# Power-Resistor-Breakout-3W-v001.net
KiCad netlist of a schematic drawn in EAGLE
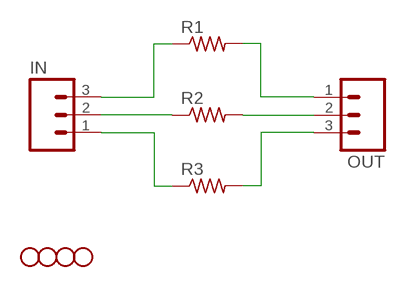
[diagram p0: schematic, sheet 1]

(export (version "E")
  (design (tool "Eeschema 10.0.6"))
  (components
    (comp (ref "IN")
      (value "M03PTH")
      (footprint "eagle-import:1X03")
      (libsource (lib "eagle-import") (part "M03PTH"))
    )
    (comp (ref "JP1")
      (value "STAND-OFF")
      (footprint "eagle-import:STAND-OFF")
      (libsource (lib "eagle-import") (part "STAND-OFF"))
    )
    (comp (ref "JP2")
      (value "STAND-OFF")
      (footprint "eagle-import:STAND-OFF")
      (libsource (lib "eagle-import") (part "STAND-OFF"))
    )
    (comp (ref "JP3")
      (value "STAND-OFF")
      (footprint "eagle-import:STAND-OFF")
      (libsource (lib "eagle-import") (part "STAND-OFF"))
    )
    (comp (ref "JP4")
      (value "STAND-OFF")
      (footprint "eagle-import:STAND-OFF")
      (libsource (lib "eagle-import") (part "STAND-OFF"))
    )
    (comp (ref "OUT")
      (value "M03PTH")
      (footprint "eagle-import:1X03")
      (libsource (lib "eagle-import") (part "M03PTH"))
    )
    (comp (ref "R1")
      (value "R-US_0411/15")
      (footprint "eagle-import:0411_15")
      (libsource (lib "eagle-import") (part "R-US_0411/15"))
    )
    (comp (ref "R2")
      (value "R-US_0411/15")
      (footprint "eagle-import:0411_15")
      (libsource (lib "eagle-import") (part "R-US_0411/15"))
    )
    (comp (ref "R3")
      (value "R-US_0411/15")
      (footprint "eagle-import:0411_15")
      (libsource (lib "eagle-import") (part "R-US_0411/15"))
    )
  )
  (nets
    (net (code "1") (name "Net-(IN-Pad1)") (class "Default")
      (node (ref "IN") (pin "1") (pinfunction "1_1") (pintype "passive"))
      (node (ref "R3") (pin "1") (pinfunction "1_1") (pintype "passive"))
    )
    (net (code "2") (name "Net-(IN-Pad2)") (class "Default")
      (node (ref "IN") (pin "2") (pinfunction "2_2") (pintype "passive"))
      (node (ref "R2") (pin "1") (pinfunction "1_1") (pintype "passive"))
    )
    (net (code "3") (name "Net-(IN-Pad3)") (class "Default")
      (node (ref "IN") (pin "3") (pinfunction "3_3") (pintype "passive"))
      (node (ref "R1") (pin "1") (pinfunction "1_1") (pintype "passive"))
    )
    (net (code "4") (name "Net-(OUT-Pad1)") (class "Default")
      (node (ref "OUT") (pin "1") (pinfunction "1_1") (pintype "passive"))
      (node (ref "R1") (pin "2") (pinfunction "2_2") (pintype "passive"))
    )
    (net (code "5") (name "Net-(OUT-Pad2)") (class "Default")
      (node (ref "OUT") (pin "2") (pinfunction "2_2") (pintype "passive"))
      (node (ref "R2") (pin "2") (pinfunction "2_2") (pintype "passive"))
    )
    (net (code "6") (name "Net-(OUT-Pad3)") (class "Default")
      (node (ref "OUT") (pin "3") (pinfunction "3_3") (pintype "passive"))
      (node (ref "R3") (pin "2") (pinfunction "2_2") (pintype "passive"))
    )
  )
)
